# 1-Schematic_h-bridge_driver_arduino.net
KiCad netlist of a schematic drawn in EasyEDA
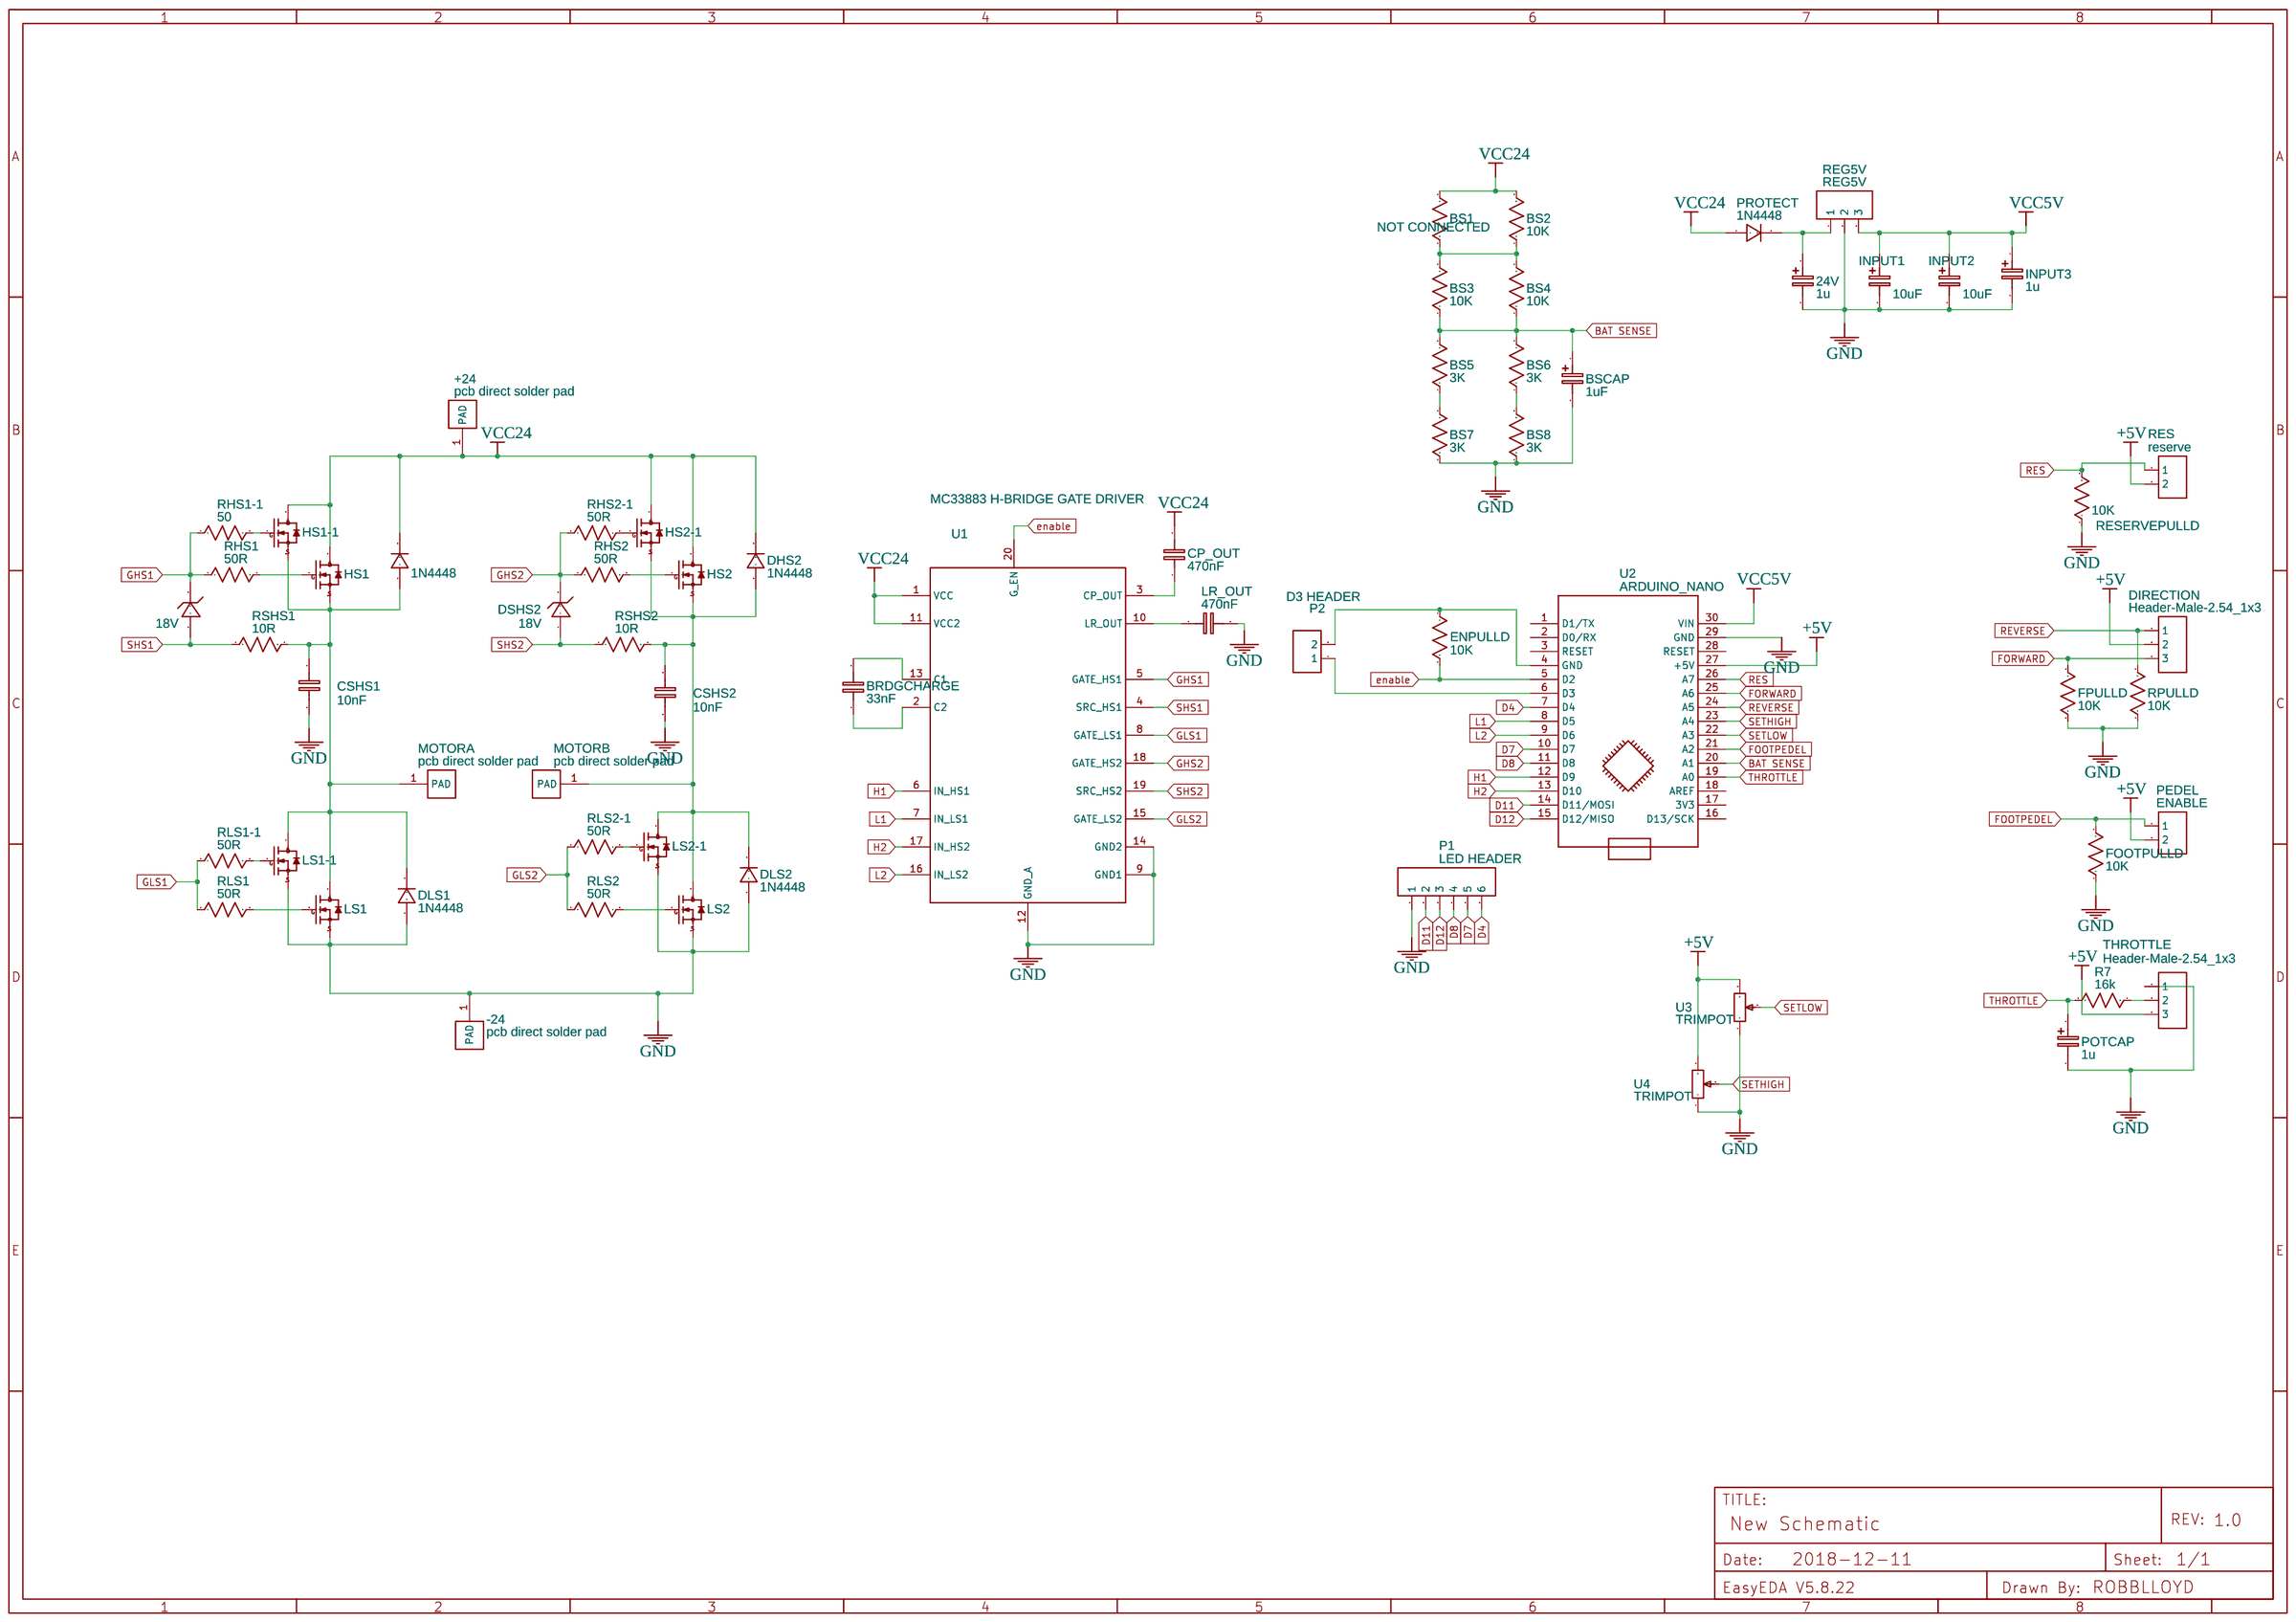
[diagram p0: schematic sheet]

(export (version "E")
  (design (tool "Eeschema 10.0.6"))
  (components
    (comp (ref "+24")
      (value "pcb direct solder pad")
      (fields (field (name "BOM_Manufacturer Part") "?") (field (name "BOM_Supplier Part") "undefined"))
      (libsource (lib "") (part "Unknown_315_330"))
    )
    (comp (ref "-24")
      (value "pcb direct solder pad")
      (fields (field (name "BOM_Manufacturer Part") "?") (field (name "BOM_Supplier Part") "undefined"))
      (libsource (lib "") (part "Unknown_340_695"))
    )
    (comp (ref "24V")
      (value "1u")
      (fields (field (name "BOM_Manufacturer Part") "?"))
      (libsource (lib "") (part "Cap_Electrolytic(TH)_D6.3XF2.5_EU"))
    )
    (comp (ref "BRDGCHARGE")
      (value "33nF")
      (fields (field (name "BOM_Manufacturer Part") "?"))
      (libsource (lib "") (part "Cap_RAD-0.1_EU_3"))
    )
    (comp (ref "BS1")
      (value "NOT CONNECTED")
      (fields (field (name "BOM_Manufacturer Part") "?"))
      (libsource (lib "") (part "Res_AXIAL-0.4(1/4W)_US_1"))
    )
    (comp (ref "BS2")
      (value "10K")
      (fields (field (name "BOM_Manufacturer Part") "?"))
      (libsource (lib "") (part "Res_AXIAL-0.4(1/4W)_US_1"))
    )
    (comp (ref "BS3")
      (value "10K")
      (fields (field (name "BOM_Manufacturer Part") "?"))
      (libsource (lib "") (part "Res_AXIAL-0.4(1/4W)_US_1"))
    )
    (comp (ref "BS4")
      (value "10K")
      (fields (field (name "BOM_Manufacturer Part") "?"))
      (libsource (lib "") (part "Res_AXIAL-0.4(1/4W)_US_1"))
    )
    (comp (ref "BS5")
      (value "3K")
      (fields (field (name "BOM_Manufacturer Part") "?"))
      (libsource (lib "") (part "Res_AXIAL-0.4(1/4W)_US_1"))
    )
    (comp (ref "BS6")
      (value "3K")
      (fields (field (name "BOM_Manufacturer Part") "?"))
      (libsource (lib "") (part "Res_AXIAL-0.4(1/4W)_US_1"))
    )
    (comp (ref "BS7")
      (value "3K")
      (fields (field (name "BOM_Manufacturer Part") "?"))
      (libsource (lib "") (part "Res_AXIAL-0.4(1/4W)_US_1"))
    )
    (comp (ref "BS8")
      (value "3K")
      (fields (field (name "BOM_Manufacturer Part") "?"))
      (libsource (lib "") (part "Res_AXIAL-0.4(1/4W)_US_1"))
    )
    (comp (ref "BSCAP")
      (value "1uF")
      (fields (field (name "BOM_Manufacturer Part") "?"))
      (libsource (lib "") (part "Cap_Electrolytic(TH)_D6.3XF2.5_EU_3"))
    )
    (comp (ref "CP_OUT")
      (value "470nF")
      (fields (field (name "BOM_Manufacturer Part") "?"))
      (libsource (lib "") (part "Cap_RAD-0.1_EU_1"))
    )
    (comp (ref "CSHS1")
      (value "10nF")
      (fields (field (name "BOM_Manufacturer Part") "?"))
      (libsource (lib "") (part "Cap_RAD-0.1_EU_2"))
    )
    (comp (ref "CSHS2")
      (value "10nF")
      (fields (field (name "BOM_Manufacturer Part") "?"))
      (libsource (lib "") (part "Cap_RAD-0.1_EU_2"))
    )
    (comp (ref "DHS1")
      (value "1N4448")
      (fields (field (name "BOM_Supplier Part") "C54037"))
      (libsource (lib "") (part "Unknown_280_395"))
    )
    (comp (ref "DHS2")
      (value "1N4448")
      (fields (field (name "BOM_Supplier Part") "C54037"))
      (libsource (lib "") (part "Unknown_535_395"))
    )
    (comp (ref "DIRECTION")
      (value "Header-Male-2.54_1x3")
      (fields
        (field (name "BOM_Manufacturer Part") "Header2.54mm 1*3P")
        (field (name "BOM_Supplier Part") "C49257")
      )
      (libsource (lib "") (part "Unknown_1540_455"))
    )
    (comp (ref "DLS1")
      (value "1N4448")
      (fields (field (name "BOM_Supplier Part") "C54037"))
      (libsource (lib "") (part "Unknown_285_635"))
    )
    (comp (ref "DLS2")
      (value "1N4448")
      (fields (field (name "BOM_Supplier Part") "C54037"))
      (libsource (lib "") (part "Unknown_530_620"))
    )
    (comp (ref "DSHS1")
      (value "18V")
      (fields
        (field (name "BOM_Manufacturer Part") "1SMB5925BT3G")
        (field (name "BOM_Supplier Part") "C53170")
      )
      (libsource (lib "") (part "Unknown_130_430"))
    )
    (comp (ref "DSHS2")
      (value "18V")
      (fields
        (field (name "BOM_Manufacturer Part") "1SMB5925BT3G")
        (field (name "BOM_Supplier Part") "C53170")
      )
      (libsource (lib "") (part "Unknown_395_430"))
    )
    (comp (ref "ENPULLD")
      (value "10K")
      (fields (field (name "BOM_Manufacturer Part") "?"))
      (libsource (lib "") (part "Res_AXIAL-0.4(1/4W)_US_9"))
    )
    (comp (ref "FOOTPULLD")
      (value "10K")
      (fields (field (name "BOM_Manufacturer Part") "?"))
      (libsource (lib "") (part "Res_AXIAL-0.4(1/4W)_US_8"))
    )
    (comp (ref "FPULLD")
      (value "10K")
      (fields (field (name "BOM_Manufacturer Part") "?"))
      (libsource (lib "") (part "Res_AXIAL-0.4(1/4W)_US_12"))
    )
    (comp (ref "HS1")
      (value "CEP6060L")
      (fields (field (name "BOM_Supplier Part") "C154171"))
      (libsource (lib "") (part "Unknown_220_405"))
    )
    (comp (ref "HS1-1")
      (value "CEP6060L")
      (fields (field (name "BOM_Supplier Part") "C154171"))
      (libsource (lib "") (part "Unknown_190_375"))
    )
    (comp (ref "HS2")
      (value "CEP6060L")
      (fields (field (name "BOM_Supplier Part") "C154171"))
      (libsource (lib "") (part "Unknown_480_405"))
    )
    (comp (ref "HS2-1")
      (value "CEP6060L")
      (fields (field (name "BOM_Supplier Part") "C154171"))
      (libsource (lib "") (part "Unknown_450_375"))
    )
    (comp (ref "INPUT1")
      (value "10uF")
      (fields (field (name "BOM_Manufacturer Part") "?"))
      (libsource (lib "") (part "Cap_Electrolytic(TH)_D6.3XF2.5_EU_2"))
    )
    (comp (ref "INPUT2")
      (value "10uF")
      (fields (field (name "BOM_Manufacturer Part") "?"))
      (libsource (lib "") (part "Cap_Electrolytic(TH)_D6.3XF2.5_EU_2"))
    )
    (comp (ref "INPUT3")
      (value "1u")
      (fields (field (name "BOM_Manufacturer Part") "?"))
      (libsource (lib "") (part "Cap_Electrolytic(TH)_D6.3XF2.5_EU_2"))
    )
    (comp (ref "LR_OUT")
      (value "470nF")
      (fields (field (name "BOM_Manufacturer Part") "?"))
      (libsource (lib "") (part "Cap_RAD-0.1_EU"))
    )
    (comp (ref "LS1")
      (value "CEP6060L")
      (fields (field (name "BOM_Supplier Part") "C154171"))
      (libsource (lib "") (part "Unknown_220_645"))
    )
    (comp (ref "LS1-1")
      (value "CEP6060L")
      (fields (field (name "BOM_Supplier Part") "C154171"))
      (libsource (lib "") (part "Unknown_190_610"))
    )
    (comp (ref "LS2")
      (value "CEP6060L")
      (fields (field (name "BOM_Supplier Part") "C154171"))
      (libsource (lib "") (part "Unknown_480_645"))
    )
    (comp (ref "LS2-1")
      (value "CEP6060L")
      (fields (field (name "BOM_Supplier Part") "C154171"))
      (libsource (lib "") (part "Unknown_455_600"))
    )
    (comp (ref "MOTORA")
      (value "pcb direct solder pad")
      (fields (field (name "BOM_Manufacturer Part") "?") (field (name "BOM_Supplier Part") "undefined"))
      (libsource (lib "") (part "Unknown_270_545"))
    )
    (comp (ref "MOTORB")
      (value "pcb direct solder pad")
      (fields (field (name "BOM_Manufacturer Part") "?") (field (name "BOM_Supplier Part") "undefined"))
      (libsource (lib "") (part "Unknown_425_520"))
    )
    (comp (ref "P1")
      (value "LED HEADER")
      (fields
        (field (name "BOM_Manufacturer Part") "Header-Male-2.54_1x6")
        (field (name "BOM_Supplier Part") "C37208")
      )
      (libsource (lib "") (part "Unknown_1030_630"))
    )
    (comp (ref "P2")
      (value "D3 HEADER")
      (fields
        (field (name "BOM_Manufacturer Part") "2.54-1*2PFemale")
        (field (name "BOM_Supplier Part") "C49661")
      )
      (libsource (lib "") (part "Unknown_935_460"))
    )
    (comp (ref "PEDEL")
      (value "ENABLE")
      (fields
        (field (name "BOM_Manufacturer Part") "2.54-1*2PFemale")
        (field (name "BOM_Supplier Part") "C49661")
      )
      (libsource (lib "") (part "Unknown_1545_590"))
    )
    (comp (ref "POTCAP")
      (value "1u")
      (fields (field (name "BOM_Manufacturer Part") "?"))
      (libsource (lib "") (part "Cap_Electrolytic(TH)_D6.3XF2.5_EU_1"))
    )
    (comp (ref "PROTECT")
      (value "1N4448")
      (fields (field (name "BOM_Supplier Part") "C54037"))
      (libsource (lib "") (part "Unknown_1250_160"))
    )
    (comp (ref "R7")
      (value "16k")
      (fields (field (name "BOM_Manufacturer Part") "?"))
      (libsource (lib "") (part "Res_AXIAL-0.4(1/4W)_US_10"))
    )
    (comp (ref "REG5V")
      (value "REG5V")
      (fields
        (field (name "BOM_Manufacturer Part") "Header2.54mm 1*3P")
        (field (name "BOM_Supplier Part") "C49257")
      )
      (libsource (lib "") (part "Unknown_1315_150"))
    )
    (comp (ref "RES")
      (value "reserve")
      (fields
        (field (name "BOM_Manufacturer Part") "2.54-1*2PFemale")
        (field (name "BOM_Supplier Part") "C49661")
      )
      (libsource (lib "") (part "Unknown_1545_335"))
    )
    (comp (ref "RESERVEPULLD")
      (value "10K")
      (fields (field (name "BOM_Manufacturer Part") "?"))
      (libsource (lib "") (part "Res_AXIAL-0.4(1/4W)_US_5"))
    )
    (comp (ref "RHS1")
      (value "50R")
      (fields (field (name "BOM_Manufacturer Part") "?"))
      (libsource (lib "") (part "Res_AXIAL-0.4(1/4W)_US_4"))
    )
    (comp (ref "RHS1-1")
      (value "50")
      (fields (field (name "BOM_Manufacturer Part") "?"))
      (libsource (lib "") (part "Res_AXIAL-0.4(1/4W)_US_7"))
    )
    (comp (ref "RHS2")
      (value "50R")
      (fields (field (name "BOM_Manufacturer Part") "?"))
      (libsource (lib "") (part "Res_AXIAL-0.4(1/4W)_US_4"))
    )
    (comp (ref "RHS2-1")
      (value "50R")
      (fields (field (name "BOM_Manufacturer Part") "?"))
      (libsource (lib "") (part "Res_AXIAL-0.4(1/4W)_US_2"))
    )
    (comp (ref "RLS1")
      (value "50R")
      (fields (field (name "BOM_Manufacturer Part") "?"))
      (libsource (lib "") (part "Res_AXIAL-0.4(1/4W)_US_11"))
    )
    (comp (ref "RLS1-1")
      (value "50R")
      (fields (field (name "BOM_Manufacturer Part") "?"))
      (libsource (lib "") (part "Res_AXIAL-0.4(1/4W)_US_13"))
    )
    (comp (ref "RLS2")
      (value "50R")
      (fields (field (name "BOM_Manufacturer Part") "?"))
      (libsource (lib "") (part "Res_AXIAL-0.4(1/4W)_US_11"))
    )
    (comp (ref "RLS2-1")
      (value "50R")
      (fields (field (name "BOM_Manufacturer Part") "?"))
      (libsource (lib "") (part "Res_AXIAL-0.4(1/4W)_US"))
    )
    (comp (ref "RPULLD")
      (value "10K")
      (fields (field (name "BOM_Manufacturer Part") "?"))
      (libsource (lib "") (part "Res_AXIAL-0.4(1/4W)_US_6"))
    )
    (comp (ref "RSHS1")
      (value "10R")
      (fields (field (name "BOM_Manufacturer Part") "?"))
      (libsource (lib "") (part "Res_AXIAL-0.4(1/4W)_US_3"))
    )
    (comp (ref "RSHS2")
      (value "10R")
      (fields (field (name "BOM_Manufacturer Part") "?"))
      (libsource (lib "") (part "Res_AXIAL-0.4(1/4W)_US_3"))
    )
    (comp (ref "THROTTLE")
      (value "Header-Male-2.54_1x3")
      (fields
        (field (name "BOM_Manufacturer Part") "Header2.54mm 1*3P")
        (field (name "BOM_Supplier Part") "C49257")
      )
      (libsource (lib "") (part "Unknown_1540_710"))
    )
    (comp (ref "U1")
      (value "MC33883 H-BRIDGE GATE DRIVER")
      (fields (field (name "BOM_Manufacturer Part") "?") (field (name "BOM_Supplier Part") "undefined"))
      (libsource (lib "") (part "Unknown_660_640"))
    )
    (comp (ref "U2")
      (value "ARDUINO_NANO")
      (fields (field (name "BOM_Manufacturer Part") "?"))
      (libsource (lib "") (part "Unknown_1160_515"))
    )
    (comp (ref "U3")
      (value "TRIMPOT")
      (fields (field (name "BOM_Manufacturer Part") "?"))
      (libsource (lib "") (part "Unknown_1220_685"))
    )
    (comp (ref "U4")
      (value "TRIMPOT")
      (fields (field (name "BOM_Manufacturer Part") "?"))
      (libsource (lib "") (part "Unknown_1190_740"))
    )
  )
  (nets
    (net (code "1") (name "+5V") (class "Default")
      (node (ref "DIRECTION") (pin "2") (pinfunction "2_2") (pintype "input"))
      (node (ref "PEDEL") (pin "2") (pinfunction "2_2") (pintype "input"))
      (node (ref "RES") (pin "2") (pinfunction "2_2") (pintype "input"))
      (node (ref "THROTTLE") (pin "3") (pinfunction "3_3") (pintype "input"))
      (node (ref "U2") (pin "27") (pinfunction "+5V_27") (pintype "unspecified"))
      (node (ref "U3") (pin "3") (pinfunction "3_3") (pintype "input"))
      (node (ref "U4") (pin "3") (pinfunction "3_3") (pintype "input"))
    )
    (net (code "2") (name "BAT SENSE") (class "Default")
      (node (ref "BS3") (pin "1") (pinfunction "1_1") (pintype "unspecified"))
      (node (ref "BS4") (pin "1") (pinfunction "1_1") (pintype "unspecified"))
      (node (ref "BS5") (pin "2") (pinfunction "2_2") (pintype "unspecified"))
      (node (ref "BS6") (pin "2") (pinfunction "2_2") (pintype "unspecified"))
      (node (ref "BSCAP") (pin "1") (pinfunction "1_1") (pintype "unspecified"))
      (node (ref "U2") (pin "20") (pinfunction "A1_20") (pintype "unspecified"))
    )
    (net (code "3") (name "D4") (class "Default")
      (node (ref "P1") (pin "6") (pinfunction "6_6") (pintype "input"))
      (node (ref "U2") (pin "7") (pinfunction "D4_7") (pintype "unspecified"))
    )
    (net (code "4") (name "D7") (class "Default")
      (node (ref "P1") (pin "5") (pinfunction "5_5") (pintype "input"))
      (node (ref "U2") (pin "10") (pinfunction "D7_10") (pintype "unspecified"))
    )
    (net (code "5") (name "D8") (class "Default")
      (node (ref "P1") (pin "4") (pinfunction "4_4") (pintype "input"))
      (node (ref "U2") (pin "11") (pinfunction "D8_11") (pintype "unspecified"))
    )
    (net (code "6") (name "D11") (class "Default")
      (node (ref "P1") (pin "2") (pinfunction "2_2") (pintype "input"))
      (node (ref "U2") (pin "14") (pinfunction "D11/MOSI_14") (pintype "unspecified"))
    )
    (net (code "7") (name "D12") (class "Default")
      (node (ref "P1") (pin "3") (pinfunction "3_3") (pintype "input"))
      (node (ref "U2") (pin "15") (pinfunction "D12/MISO_15") (pintype "unspecified"))
    )
    (net (code "8") (name "FOOTPEDEL") (class "Default")
      (node (ref "FOOTPULLD") (pin "2") (pinfunction "2_2") (pintype "unspecified"))
      (node (ref "PEDEL") (pin "1") (pinfunction "1_1") (pintype "input"))
      (node (ref "U2") (pin "21") (pinfunction "A2_21") (pintype "unspecified"))
    )
    (net (code "9") (name "FORWARD") (class "Default")
      (node (ref "DIRECTION") (pin "3") (pinfunction "3_3") (pintype "input"))
      (node (ref "FPULLD") (pin "2") (pinfunction "2_2") (pintype "unspecified"))
      (node (ref "U2") (pin "25") (pinfunction "A6_25") (pintype "unspecified"))
    )
    (net (code "10") (name "GHS1") (class "Default")
      (node (ref "DSHS1") (pin "2") (pinfunction "K_2") (pintype "unspecified"))
      (node (ref "RHS1") (pin "1") (pinfunction "1_1") (pintype "unspecified"))
      (node (ref "RHS1-1") (pin "1") (pinfunction "1_1") (pintype "unspecified"))
      (node (ref "U1") (pin "5") (pinfunction "GATE_HS1_5") (pintype "unspecified"))
    )
    (net (code "11") (name "GHS2") (class "Default")
      (node (ref "DSHS2") (pin "2") (pinfunction "K_2") (pintype "unspecified"))
      (node (ref "RHS2") (pin "1") (pinfunction "1_1") (pintype "unspecified"))
      (node (ref "RHS2-1") (pin "1") (pinfunction "1_1") (pintype "unspecified"))
      (node (ref "U1") (pin "18") (pinfunction "GATE_HS2_18") (pintype "unspecified"))
    )
    (net (code "12") (name "GLS1") (class "Default")
      (node (ref "RLS1") (pin "1") (pinfunction "1_1") (pintype "unspecified"))
      (node (ref "RLS1-1") (pin "1") (pinfunction "1_1") (pintype "unspecified"))
      (node (ref "U1") (pin "8") (pinfunction "GATE_LS1_8") (pintype "unspecified"))
    )
    (net (code "13") (name "GLS2") (class "Default")
      (node (ref "RLS2") (pin "1") (pinfunction "1_1") (pintype "unspecified"))
      (node (ref "RLS2-1") (pin "1") (pinfunction "1_1") (pintype "unspecified"))
      (node (ref "U1") (pin "15") (pinfunction "GATE_LS2_15") (pintype "unspecified"))
    )
    (net (code "14") (name "GND") (class "Default")
      (node (ref "-24") (pin "1") (pinfunction "PAD_1") (pintype "unspecified"))
      (node (ref "24V") (pin "2") (pinfunction "2_2") (pintype "unspecified"))
      (node (ref "BS7") (pin "1") (pinfunction "1_1") (pintype "unspecified"))
      (node (ref "BS8") (pin "1") (pinfunction "1_1") (pintype "unspecified"))
      (node (ref "BSCAP") (pin "2") (pinfunction "2_2") (pintype "unspecified"))
      (node (ref "CSHS1") (pin "2") (pinfunction "2_2") (pintype "unspecified"))
      (node (ref "CSHS2") (pin "2") (pinfunction "2_2") (pintype "unspecified"))
      (node (ref "DLS1") (pin "1") (pinfunction "A_1") (pintype "unspecified"))
      (node (ref "DLS2") (pin "1") (pinfunction "A_1") (pintype "unspecified"))
      (node (ref "FOOTPULLD") (pin "1") (pinfunction "1_1") (pintype "unspecified"))
      (node (ref "FPULLD") (pin "1") (pinfunction "1_1") (pintype "unspecified"))
      (node (ref "INPUT1") (pin "2") (pinfunction "2_2") (pintype "unspecified"))
      (node (ref "INPUT2") (pin "2") (pinfunction "2_2") (pintype "unspecified"))
      (node (ref "INPUT3") (pin "2") (pinfunction "2_2") (pintype "unspecified"))
      (node (ref "LR_OUT") (pin "2") (pinfunction "2_2") (pintype "unspecified"))
      (node (ref "LS1") (pin "3") (pinfunction "S_3") (pintype "unspecified"))
      (node (ref "LS1-1") (pin "3") (pinfunction "S_3") (pintype "unspecified"))
      (node (ref "LS2") (pin "3") (pinfunction "S_3") (pintype "unspecified"))
      (node (ref "LS2-1") (pin "3") (pinfunction "S_3") (pintype "unspecified"))
      (node (ref "P1") (pin "1") (pinfunction "1_1") (pintype "input"))
      (node (ref "POTCAP") (pin "2") (pinfunction "2_2") (pintype "unspecified"))
      (node (ref "REG5V") (pin "2") (pinfunction "2_2") (pintype "input"))
      (node (ref "RESERVEPULLD") (pin "1") (pinfunction "1_1") (pintype "unspecified"))
      (node (ref "RPULLD") (pin "1") (pinfunction "1_1") (pintype "unspecified"))
      (node (ref "THROTTLE") (pin "1") (pinfunction "1_1") (pintype "input"))
      (node (ref "U1") (pin "12") (pinfunction "GND_A_12") (pintype "unspecified"))
      (node (ref "U1") (pin "14") (pinfunction "GND2_14") (pintype "unspecified"))
      (node (ref "U1") (pin "9") (pinfunction "GND1_9") (pintype "unspecified"))
      (node (ref "U2") (pin "29") (pinfunction "GND_29") (pintype "unspecified"))
      (node (ref "U3") (pin "1") (pinfunction "1_1") (pintype "input"))
      (node (ref "U4") (pin "1") (pinfunction "1_1") (pintype "input"))
    )
    (net (code "15") (name "H1") (class "Default")
      (node (ref "U1") (pin "6") (pinfunction "IN_HS1_6") (pintype "unspecified"))
      (node (ref "U2") (pin "12") (pinfunction "D9_12") (pintype "unspecified"))
    )
    (net (code "16") (name "H2") (class "Default")
      (node (ref "U1") (pin "17") (pinfunction "IN_HS2_17") (pintype "unspecified"))
      (node (ref "U2") (pin "13") (pinfunction "D10_13") (pintype "unspecified"))
    )
    (net (code "17") (name "L1") (class "Default")
      (node (ref "U1") (pin "7") (pinfunction "IN_LS1_7") (pintype "unspecified"))
      (node (ref "U2") (pin "8") (pinfunction "D5_8") (pintype "unspecified"))
    )
    (net (code "18") (name "L2") (class "Default")
      (node (ref "U1") (pin "16") (pinfunction "IN_LS2_16") (pintype "unspecified"))
      (node (ref "U2") (pin "9") (pinfunction "D6_9") (pintype "unspecified"))
    )
    (net (code "19") (name "Net-(BS1-Pad1)") (class "Default")
      (node (ref "BS1") (pin "1") (pinfunction "1_1") (pintype "unspecified"))
      (node (ref "BS2") (pin "1") (pinfunction "1_1") (pintype "unspecified"))
      (node (ref "BS3") (pin "2") (pinfunction "2_2") (pintype "unspecified"))
      (node (ref "BS4") (pin "2") (pinfunction "2_2") (pintype "unspecified"))
    )
    (net (code "20") (name "Net-(BS5-Pad1)") (class "Default")
      (node (ref "BS5") (pin "1") (pinfunction "1_1") (pintype "unspecified"))
      (node (ref "BS7") (pin "2") (pinfunction "2_2") (pintype "unspecified"))
    )
    (net (code "21") (name "Net-(BS6-Pad1)") (class "Default")
      (node (ref "BS6") (pin "1") (pinfunction "1_1") (pintype "unspecified"))
      (node (ref "BS8") (pin "2") (pinfunction "2_2") (pintype "unspecified"))
    )
    (net (code "22") (name "Net-(DHS1-A)") (class "Default")
      (node (ref "CSHS1") (pin "1") (pinfunction "1_1") (pintype "unspecified"))
      (node (ref "DHS1") (pin "1") (pinfunction "A_1") (pintype "unspecified"))
      (node (ref "DLS1") (pin "2") (pinfunction "K_2") (pintype "unspecified"))
      (node (ref "HS1") (pin "3") (pinfunction "S_3") (pintype "unspecified"))
      (node (ref "HS1-1") (pin "3") (pinfunction "S_3") (pintype "unspecified"))
      (node (ref "LS1") (pin "2") (pinfunction "D_2") (pintype "unspecified"))
      (node (ref "LS1-1") (pin "2") (pinfunction "D_2") (pintype "unspecified"))
      (node (ref "MOTORA") (pin "1") (pinfunction "PAD_1") (pintype "unspecified"))
      (node (ref "RSHS1") (pin "2") (pinfunction "2_2") (pintype "unspecified"))
    )
    (net (code "23") (name "Net-(DHS2-A)") (class "Default")
      (node (ref "CSHS2") (pin "1") (pinfunction "1_1") (pintype "unspecified"))
      (node (ref "DHS2") (pin "1") (pinfunction "A_1") (pintype "unspecified"))
      (node (ref "DLS2") (pin "2") (pinfunction "K_2") (pintype "unspecified"))
      (node (ref "HS2") (pin "3") (pinfunction "S_3") (pintype "unspecified"))
      (node (ref "HS2-1") (pin "3") (pinfunction "S_3") (pintype "unspecified"))
      (node (ref "LS2") (pin "2") (pinfunction "D_2") (pintype "unspecified"))
      (node (ref "LS2-1") (pin "2") (pinfunction "D_2") (pintype "unspecified"))
      (node (ref "MOTORB") (pin "1") (pinfunction "PAD_1") (pintype "unspecified"))
      (node (ref "RSHS2") (pin "2") (pinfunction "2_2") (pintype "unspecified"))
    )
    (net (code "24") (name "Net-(ENPULLD-Pad1)") (class "Default")
      (node (ref "ENPULLD") (pin "1") (pinfunction "1_1") (pintype "unspecified"))
      (node (ref "P2") (pin "2") (pinfunction "2_2") (pintype "input"))
      (node (ref "U2") (pin "4") (pinfunction "GND_4") (pintype "unspecified"))
    )
    (net (code "25") (name "Net-(HS1-1-G)") (class "Default")
      (node (ref "HS1-1") (pin "1") (pinfunction "G_1") (pintype "unspecified"))
      (node (ref "RHS1-1") (pin "2") (pinfunction "2_2") (pintype "unspecified"))
    )
    (net (code "26") (name "Net-(HS1-G)") (class "Default")
      (node (ref "HS1") (pin "1") (pinfunction "G_1") (pintype "unspecified"))
      (node (ref "RHS1") (pin "2") (pinfunction "2_2") (pintype "unspecified"))
    )
    (net (code "27") (name "Net-(HS2-1-G)") (class "Default")
      (node (ref "HS2-1") (pin "1") (pinfunction "G_1") (pintype "unspecified"))
      (node (ref "RHS2-1") (pin "2") (pinfunction "2_2") (pintype "unspecified"))
    )
    (net (code "28") (name "Net-(HS2-G)") (class "Default")
      (node (ref "HS2") (pin "1") (pinfunction "G_1") (pintype "unspecified"))
      (node (ref "RHS2") (pin "2") (pinfunction "2_2") (pintype "unspecified"))
    )
    (net (code "29") (name "Net-(LS1-1-G)") (class "Default")
      (node (ref "LS1-1") (pin "1") (pinfunction "G_1") (pintype "unspecified"))
      (node (ref "RLS1-1") (pin "2") (pinfunction "2_2") (pintype "unspecified"))
    )
    (net (code "30") (name "Net-(LS1-G)") (class "Default")
      (node (ref "LS1") (pin "1") (pinfunction "G_1") (pintype "unspecified"))
      (node (ref "RLS1") (pin "2") (pinfunction "2_2") (pintype "unspecified"))
    )
    (net (code "31") (name "Net-(LS2-1-G)") (class "Default")
      (node (ref "LS2-1") (pin "1") (pinfunction "G_1") (pintype "unspecified"))
      (node (ref "RLS2-1") (pin "2") (pinfunction "2_2") (pintype "unspecified"))
    )
    (net (code "32") (name "Net-(LS2-G)") (class "Default")
      (node (ref "LS2") (pin "1") (pinfunction "G_1") (pintype "unspecified"))
      (node (ref "RLS2") (pin "2") (pinfunction "2_2") (pintype "unspecified"))
    )
    (net (code "33") (name "Net-(PROTECT-K)") (class "Default")
      (node (ref "24V") (pin "1") (pinfunction "1_1") (pintype "unspecified"))
      (node (ref "PROTECT") (pin "2") (pinfunction "K_2") (pintype "unspecified"))
      (node (ref "REG5V") (pin "1") (pinfunction "1_1") (pintype "input"))
    )
    (net (code "34") (name "Net-(R7-Pad1)") (class "Default")
      (node (ref "R7") (pin "1") (pinfunction "1_1") (pintype "unspecified"))
      (node (ref "THROTTLE") (pin "2") (pinfunction "2_2") (pintype "input"))
    )
    (net (code "35") (name "Net-(U1-C1)") (class "Default")
      (node (ref "BRDGCHARGE") (pin "2") (pinfunction "2_2") (pintype "unspecified"))
      (node (ref "U1") (pin "13") (pinfunction "C1_13") (pintype "unspecified"))
    )
    (net (code "36") (name "Net-(U1-C2)") (class "Default")
      (node (ref "BRDGCHARGE") (pin "1") (pinfunction "1_1") (pintype "unspecified"))
      (node (ref "U1") (pin "2") (pinfunction "C2_2") (pintype "unspecified"))
    )
    (net (code "37") (name "Net-(U1-CP_OUT)") (class "Default")
      (node (ref "CP_OUT") (pin "1") (pinfunction "1_1") (pintype "unspecified"))
      (node (ref "U1") (pin "3") (pinfunction "CP_OUT_3") (pintype "unspecified"))
    )
    (net (code "38") (name "Net-(U1-LR_OUT)") (class "Default")
      (node (ref "LR_OUT") (pin "1") (pinfunction "1_1") (pintype "unspecified"))
      (node (ref "U1") (pin "10") (pinfunction "LR_OUT_10") (pintype "unspecified"))
    )
    (net (code "39") (name "Net-(U2-D3)") (class "Default")
      (node (ref "P2") (pin "1") (pinfunction "1_1") (pintype "input"))
      (node (ref "U2") (pin "6") (pinfunction "D3_6") (pintype "unspecified"))
    )
    (net (code "40") (name "RES") (class "Default")
      (node (ref "RES") (pin "1") (pinfunction "1_1") (pintype "input"))
      (node (ref "RESERVEPULLD") (pin "2") (pinfunction "2_2") (pintype "unspecified"))
      (node (ref "U2") (pin "26") (pinfunction "A7_26") (pintype "unspecified"))
    )
    (net (code "41") (name "REVERSE") (class "Default")
      (node (ref "DIRECTION") (pin "1") (pinfunction "1_1") (pintype "input"))
      (node (ref "RPULLD") (pin "2") (pinfunction "2_2") (pintype "unspecified"))
      (node (ref "U2") (pin "24") (pinfunction "A5_24") (pintype "unspecified"))
    )
    (net (code "42") (name "SETHIGH") (class "Default")
      (node (ref "U2") (pin "23") (pinfunction "A4_23") (pintype "unspecified"))
      (node (ref "U4") (pin "2") (pinfunction "2_2") (pintype "input"))
    )
    (net (code "43") (name "SETLOW") (class "Default")
      (node (ref "U2") (pin "22") (pinfunction "A3_22") (pintype "unspecified"))
      (node (ref "U3") (pin "2") (pinfunction "2_2") (pintype "input"))
    )
    (net (code "44") (name "SHS1") (class "Default")
      (node (ref "DSHS1") (pin "1") (pinfunction "A_1") (pintype "unspecified"))
      (node (ref "RSHS1") (pin "1") (pinfunction "1_1") (pintype "unspecified"))
      (node (ref "U1") (pin "4") (pinfunction "SRC_HS1_4") (pintype "unspecified"))
    )
    (net (code "45") (name "SHS2") (class "Default")
      (node (ref "DSHS2") (pin "1") (pinfunction "A_1") (pintype "unspecified"))
      (node (ref "RSHS2") (pin "1") (pinfunction "1_1") (pintype "unspecified"))
      (node (ref "U1") (pin "19") (pinfunction "SRC_HS2_19") (pintype "unspecified"))
    )
    (net (code "46") (name "THROTTLE") (class "Default")
      (node (ref "POTCAP") (pin "1") (pinfunction "1_1") (pintype "unspecified"))
      (node (ref "R7") (pin "2") (pinfunction "2_2") (pintype "unspecified"))
      (node (ref "U2") (pin "19") (pinfunction "A0_19") (pintype "unspecified"))
    )
    (net (code "47") (name "VCC5V") (class "Default")
      (node (ref "INPUT1") (pin "1") (pinfunction "1_1") (pintype "unspecified"))
      (node (ref "INPUT2") (pin "1") (pinfunction "1_1") (pintype "unspecified"))
      (node (ref "INPUT3") (pin "1") (pinfunction "1_1") (pintype "unspecified"))
      (node (ref "REG5V") (pin "3") (pinfunction "3_3") (pintype "input"))
      (node (ref "U2") (pin "30") (pinfunction "VIN_30") (pintype "unspecified"))
    )
    (net (code "48") (name "VCC24") (class "Default")
      (node (ref "+24") (pin "1") (pinfunction "PAD_1") (pintype "unspecified"))
      (node (ref "BS1") (pin "2") (pinfunction "2_2") (pintype "unspecified"))
      (node (ref "BS2") (pin "2") (pinfunction "2_2") (pintype "unspecified"))
      (node (ref "CP_OUT") (pin "2") (pinfunction "2_2") (pintype "unspecified"))
      (node (ref "DHS1") (pin "2") (pinfunction "K_2") (pintype "unspecified"))
      (node (ref "DHS2") (pin "2") (pinfunction "K_2") (pintype "unspecified"))
      (node (ref "HS1") (pin "2") (pinfunction "D_2") (pintype "unspecified"))
      (node (ref "HS1-1") (pin "2") (pinfunction "D_2") (pintype "unspecified"))
      (node (ref "HS2") (pin "2") (pinfunction "D_2") (pintype "unspecified"))
      (node (ref "HS2-1") (pin "2") (pinfunction "D_2") (pintype "unspecified"))
      (node (ref "PROTECT") (pin "1") (pinfunction "A_1") (pintype "unspecified"))
      (node (ref "U1") (pin "1") (pinfunction "VCC_1") (pintype "unspecified"))
      (node (ref "U1") (pin "11") (pinfunction "VCC2_11") (pintype "unspecified"))
    )
    (net (code "49") (name "enable") (class "Default")
      (node (ref "ENPULLD") (pin "2") (pinfunction "2_2") (pintype "unspecified"))
      (node (ref "U1") (pin "20") (pinfunction "G_EN_20") (pintype "unspecified"))
      (node (ref "U2") (pin "5") (pinfunction "D2_5") (pintype "unspecified"))
    )
    (net (code "50") (name "unconnected-(U2-3V3-Pad17)") (class "Default")
      (node (ref "U2") (pin "17") (pinfunction "3V3_17") (pintype "unspecified"))
    )
    (net (code "51") (name "unconnected-(U2-AREF-Pad18)") (class "Default")
      (node (ref "U2") (pin "18") (pinfunction "AREF_18") (pintype "unspecified"))
    )
    (net (code "52") (name "unconnected-(U2-D0{slash}RX-Pad2)") (class "Default")
      (node (ref "U2") (pin "2") (pinfunction "D0/RX_2") (pintype "unspecified"))
    )
    (net (code "53") (name "unconnected-(U2-D1{slash}TX-Pad1)") (class "Default")
      (node (ref "U2") (pin "1") (pinfunction "D1/TX_1") (pintype "unspecified"))
    )
    (net (code "54") (name "unconnected-(U2-D13{slash}SCK-Pad16)") (class "Default")
      (node (ref "U2") (pin "16") (pinfunction "D13/SCK_16") (pintype "unspecified"))
    )
    (net (code "55") (name "unconnected-(U2-RESET-Pad3)") (class "Default")
      (node (ref "U2") (pin "3") (pinfunction "RESET_3") (pintype "unspecified"))
    )
    (net (code "56") (name "unconnected-(U2-RESET-Pad28)") (class "Default")
      (node (ref "U2") (pin "28") (pinfunction "RESET_28") (pintype "unspecified"))
    )
  )
)
